# esp8266-3cell.net
KiCad netlist of a schematic drawn in EAGLE
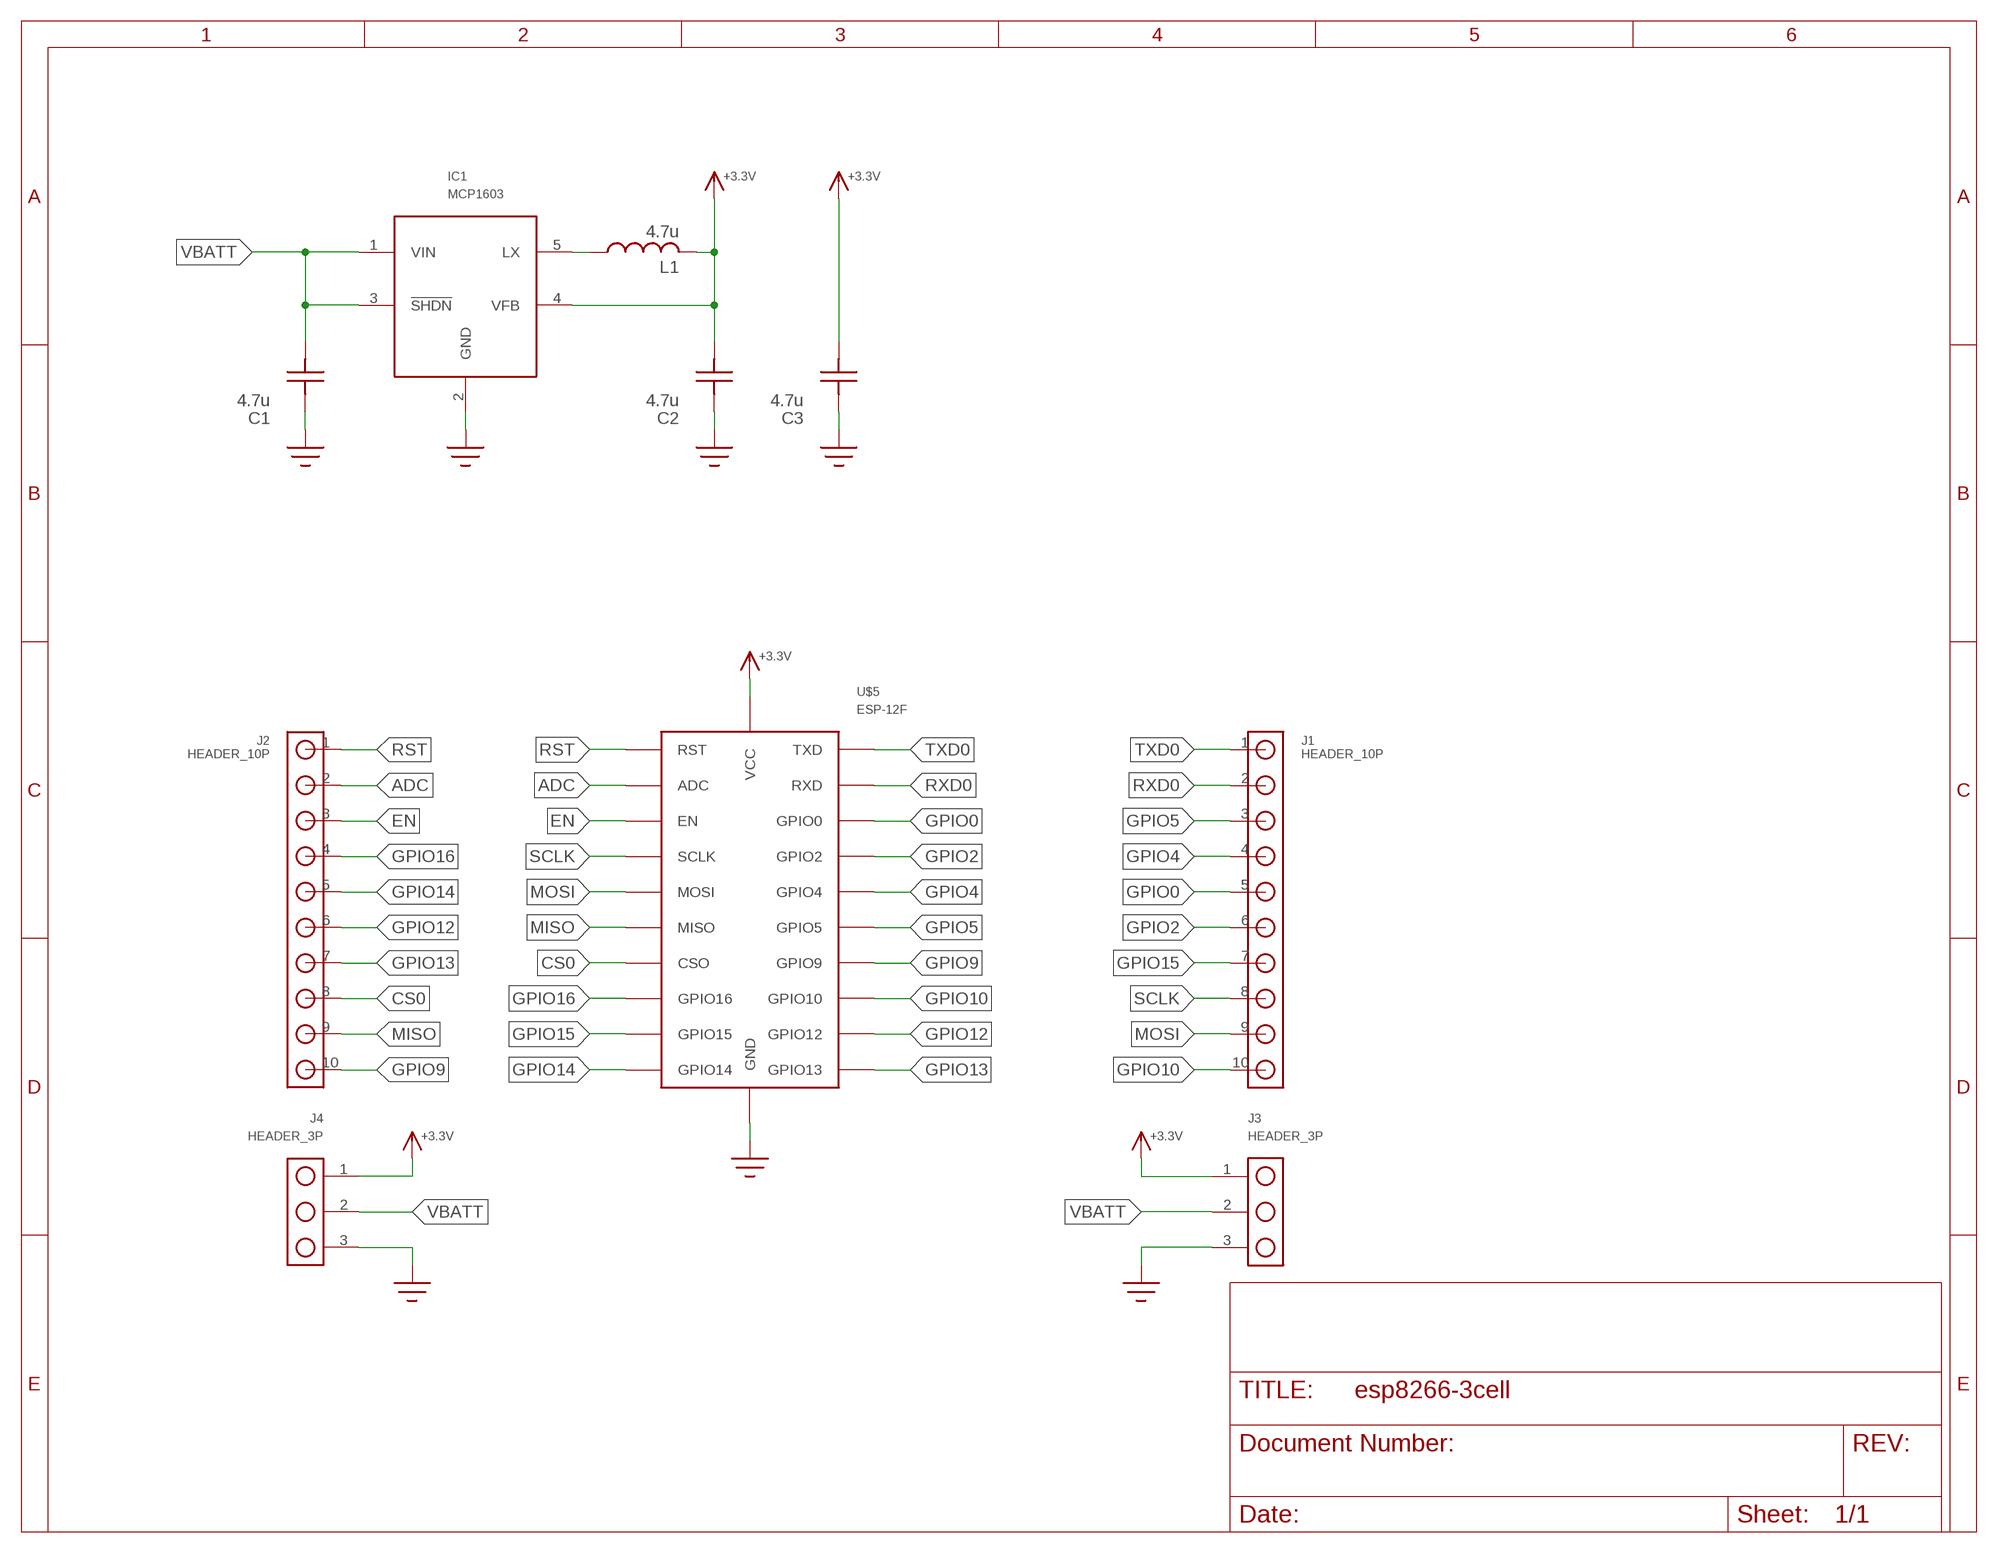
[diagram p0: schematic, sheet 1]

(export (version "E")
  (design (tool "Eeschema 10.0.6"))
  (components
    (comp (ref "C1")
      (value "4.7u")
      (footprint "eagle-import:0805")
      (libsource (lib "eagle-import") (part "C0805"))
    )
    (comp (ref "C2")
      (value "4.7u")
      (footprint "eagle-import:0805")
      (libsource (lib "eagle-import") (part "C0805"))
    )
    (comp (ref "C3")
      (value "4.7u")
      (footprint "eagle-import:0805")
      (libsource (lib "eagle-import") (part "C0805"))
    )
    (comp (ref "IC1")
      (value "MCP1603")
      (footprint "eagle-import:SOT23-5")
      (libsource (lib "eagle-import") (part "MCP1603"))
    )
    (comp (ref "J1")
      (value "HEADER_10P")
      (footprint "eagle-import:HEADER_10P")
      (libsource (lib "eagle-import") (part "HEADER_10P"))
    )
    (comp (ref "J2")
      (value "HEADER_10P")
      (footprint "eagle-import:HEADER_10P")
      (libsource (lib "eagle-import") (part "HEADER_10P"))
    )
    (comp (ref "J3")
      (value "HEADER_3P")
      (footprint "eagle-import:HEADER_3P")
      (libsource (lib "eagle-import") (part "HEADER_3P"))
    )
    (comp (ref "J4")
      (value "HEADER_3P")
      (footprint "eagle-import:HEADER_3P")
      (libsource (lib "eagle-import") (part "HEADER_3P"))
    )
    (comp (ref "L1")
      (value "4.7u")
      (footprint "eagle-import:L24X24")
      (libsource (lib "eagle-import") (part "L"))
    )
    (comp (ref "U$5")
      (value "ESP-12F")
      (footprint "eagle-import:ESP-12F")
      (libsource (lib "eagle-import") (part "ESP-12F"))
    )
  )
  (nets
    (net (code "1") (name "+3.3V") (class "Default")
      (node (ref "C2") (pin "P$1") (pinfunction "P$1_P$1") (pintype "bidirectional"))
      (node (ref "C3") (pin "P$1") (pinfunction "P$1_P$1") (pintype "bidirectional"))
      (node (ref "IC1") (pin "4") (pinfunction "VFB_4") (pintype "bidirectional"))
      (node (ref "J3") (pin "1") (pinfunction "1_1") (pintype "bidirectional"))
      (node (ref "J4") (pin "1") (pinfunction "1_1") (pintype "bidirectional"))
      (node (ref "L1") (pin "2") (pinfunction "2_2") (pintype "passive"))
      (node (ref "U$5") (pin "VCC") (pinfunction "VCC_VCC") (pintype "bidirectional"))
    )
    (net (code "2") (name "ADC") (class "Default")
      (node (ref "J2") (pin "2") (pinfunction "2_2") (pintype "bidirectional"))
      (node (ref "U$5") (pin "ADC") (pinfunction "ADC_ADC") (pintype "bidirectional"))
    )
    (net (code "3") (name "CS0") (class "Default")
      (node (ref "J2") (pin "8") (pinfunction "8_8") (pintype "bidirectional"))
      (node (ref "U$5") (pin "CSO") (pinfunction "CSO_CSO") (pintype "bidirectional"))
    )
    (net (code "4") (name "EN") (class "Default")
      (node (ref "J2") (pin "3") (pinfunction "3_3") (pintype "bidirectional"))
      (node (ref "U$5") (pin "EN") (pinfunction "EN_EN") (pintype "bidirectional"))
    )
    (net (code "5") (name "GND") (class "Default")
      (node (ref "C1") (pin "P$2") (pinfunction "P$2_P$2") (pintype "bidirectional"))
      (node (ref "C2") (pin "P$2") (pinfunction "P$2_P$2") (pintype "bidirectional"))
      (node (ref "C3") (pin "P$2") (pinfunction "P$2_P$2") (pintype "bidirectional"))
      (node (ref "IC1") (pin "2") (pinfunction "GND_2") (pintype "bidirectional"))
      (node (ref "J3") (pin "3") (pinfunction "3_3") (pintype "bidirectional"))
      (node (ref "J4") (pin "3") (pinfunction "3_3") (pintype "bidirectional"))
      (node (ref "U$5") (pin "GND") (pinfunction "GND_GND") (pintype "bidirectional"))
    )
    (net (code "6") (name "GPIO0") (class "Default")
      (node (ref "J1") (pin "5") (pinfunction "5_5") (pintype "bidirectional"))
      (node (ref "U$5") (pin "GPIO0") (pinfunction "GPIO0_GPIO0") (pintype "bidirectional"))
    )
    (net (code "7") (name "GPIO2") (class "Default")
      (node (ref "J1") (pin "6") (pinfunction "6_6") (pintype "bidirectional"))
      (node (ref "U$5") (pin "GPIO2") (pinfunction "GPIO2_GPIO2") (pintype "bidirectional"))
    )
    (net (code "8") (name "GPIO4") (class "Default")
      (node (ref "J1") (pin "4") (pinfunction "4_4") (pintype "bidirectional"))
      (node (ref "U$5") (pin "GPIO4") (pinfunction "GPIO4_GPIO4") (pintype "bidirectional"))
    )
    (net (code "9") (name "GPIO5") (class "Default")
      (node (ref "J1") (pin "3") (pinfunction "3_3") (pintype "bidirectional"))
      (node (ref "U$5") (pin "GPIO5") (pinfunction "GPIO5_GPIO5") (pintype "bidirectional"))
    )
    (net (code "10") (name "GPIO9") (class "Default")
      (node (ref "J2") (pin "10") (pinfunction "10_10") (pintype "bidirectional"))
      (node (ref "U$5") (pin "GPIO9") (pinfunction "GPIO9_GPIO9") (pintype "bidirectional"))
    )
    (net (code "11") (name "GPIO10") (class "Default")
      (node (ref "J1") (pin "10") (pinfunction "10_10") (pintype "bidirectional"))
      (node (ref "U$5") (pin "GPIO10") (pinfunction "GPIO10_GPIO10") (pintype "bidirectional"))
    )
    (net (code "12") (name "GPIO12") (class "Default")
      (node (ref "J2") (pin "6") (pinfunction "6_6") (pintype "bidirectional"))
      (node (ref "U$5") (pin "GPIO12") (pinfunction "GPIO12_GPIO12") (pintype "bidirectional"))
    )
    (net (code "13") (name "GPIO13") (class "Default")
      (node (ref "J2") (pin "7") (pinfunction "7_7") (pintype "bidirectional"))
      (node (ref "U$5") (pin "GPIO13") (pinfunction "GPIO13_GPIO13") (pintype "bidirectional"))
    )
    (net (code "14") (name "GPIO14") (class "Default")
      (node (ref "J2") (pin "5") (pinfunction "5_5") (pintype "bidirectional"))
      (node (ref "U$5") (pin "GPIO14") (pinfunction "GPIO14_GPIO14") (pintype "bidirectional"))
    )
    (net (code "15") (name "GPIO15") (class "Default")
      (node (ref "J1") (pin "7") (pinfunction "7_7") (pintype "bidirectional"))
      (node (ref "U$5") (pin "GPIO15") (pinfunction "GPIO15_GPIO15") (pintype "bidirectional"))
    )
    (net (code "16") (name "GPIO16") (class "Default")
      (node (ref "J2") (pin "4") (pinfunction "4_4") (pintype "bidirectional"))
      (node (ref "U$5") (pin "GPIO16") (pinfunction "GPIO16_GPIO16") (pintype "bidirectional"))
    )
    (net (code "17") (name "MISO") (class "Default")
      (node (ref "J2") (pin "9") (pinfunction "9_9") (pintype "bidirectional"))
      (node (ref "U$5") (pin "MISO") (pinfunction "MISO_MISO") (pintype "bidirectional"))
    )
    (net (code "18") (name "MOSI") (class "Default")
      (node (ref "J1") (pin "9") (pinfunction "9_9") (pintype "bidirectional"))
      (node (ref "U$5") (pin "MOSI") (pinfunction "MOSI_MOSI") (pintype "bidirectional"))
    )
    (net (code "19") (name "Net-(IC1-LX)") (class "Default")
      (node (ref "IC1") (pin "5") (pinfunction "LX_5") (pintype "bidirectional"))
      (node (ref "L1") (pin "1") (pinfunction "1_1") (pintype "passive"))
    )
    (net (code "20") (name "RST") (class "Default")
      (node (ref "J2") (pin "1") (pinfunction "1_1") (pintype "bidirectional"))
      (node (ref "U$5") (pin "RST") (pinfunction "RST_RST") (pintype "bidirectional"))
    )
    (net (code "21") (name "RXD0") (class "Default")
      (node (ref "J1") (pin "2") (pinfunction "2_2") (pintype "bidirectional"))
      (node (ref "U$5") (pin "RXD") (pinfunction "RXD_RXD") (pintype "bidirectional"))
    )
    (net (code "22") (name "SCLK") (class "Default")
      (node (ref "J1") (pin "8") (pinfunction "8_8") (pintype "bidirectional"))
      (node (ref "U$5") (pin "SCLK") (pinfunction "SCLK_SCLK") (pintype "bidirectional"))
    )
    (net (code "23") (name "TXD0") (class "Default")
      (node (ref "J1") (pin "1") (pinfunction "1_1") (pintype "bidirectional"))
      (node (ref "U$5") (pin "TXD") (pinfunction "TXD_TXD") (pintype "bidirectional"))
    )
    (net (code "24") (name "VBATT") (class "Default")
      (node (ref "C1") (pin "P$1") (pinfunction "P$1_P$1") (pintype "bidirectional"))
      (node (ref "IC1") (pin "1") (pinfunction "VIN_1") (pintype "bidirectional"))
      (node (ref "IC1") (pin "3") (pinfunction "~{SHDN}_3") (pintype "bidirectional"))
      (node (ref "J3") (pin "2") (pinfunction "2_2") (pintype "bidirectional"))
      (node (ref "J4") (pin "2") (pinfunction "2_2") (pintype "bidirectional"))
    )
  )
)
